# TELM0002ADC.net
KiCad netlist of a schematic drawn in Altium Designer
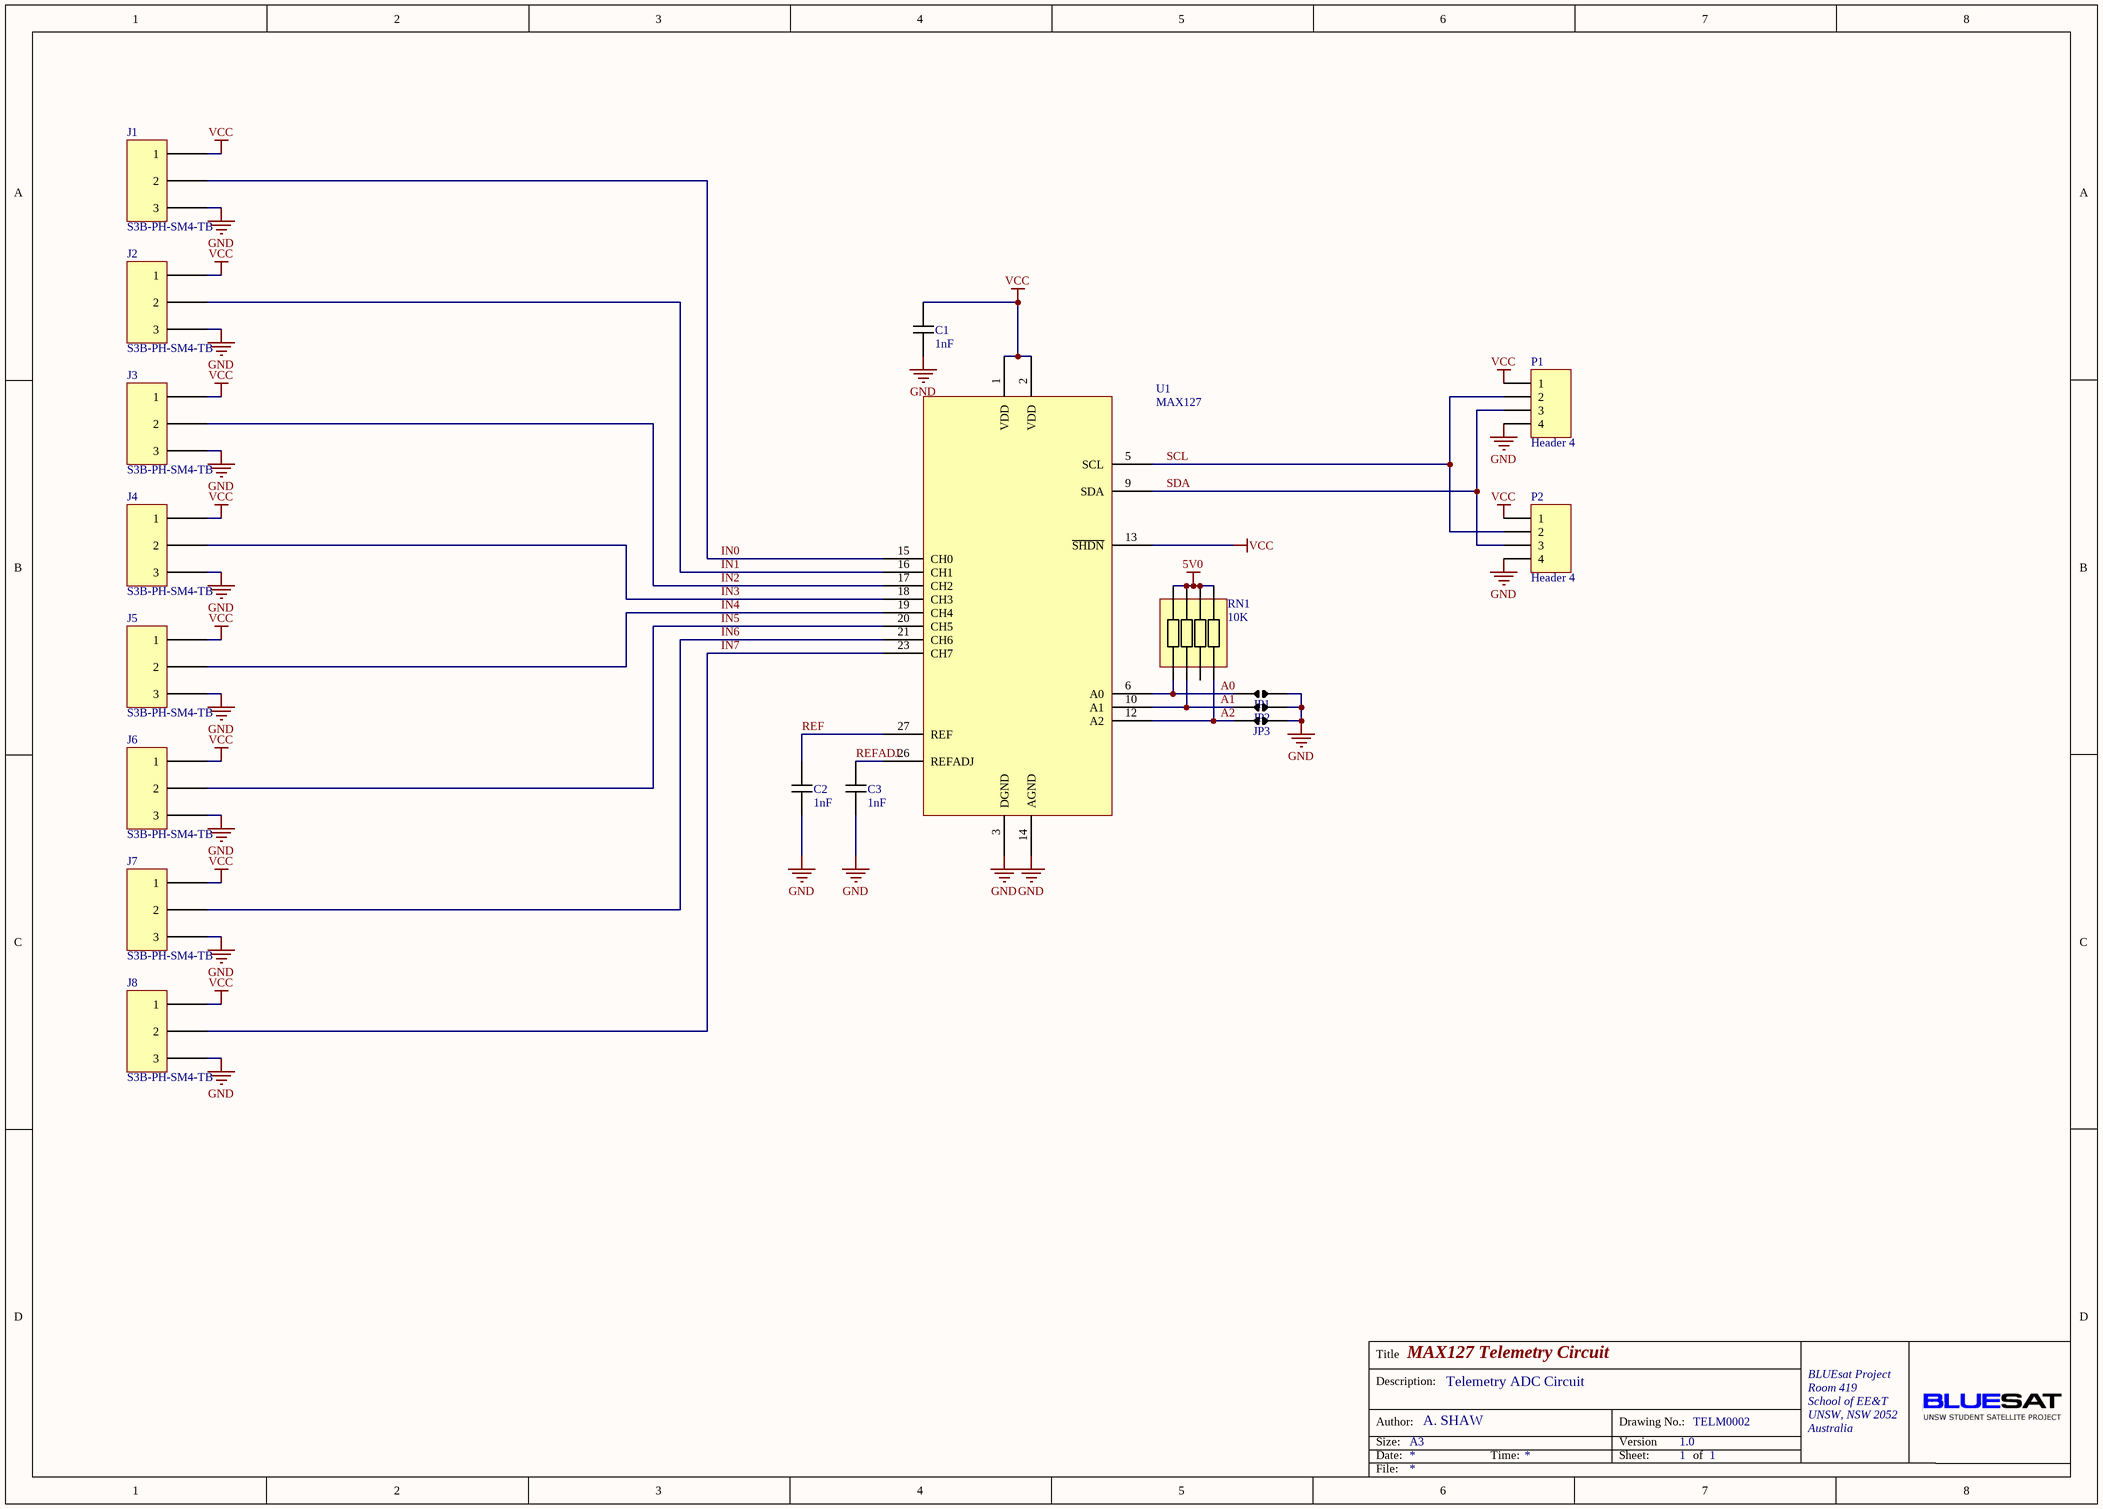
[diagram p0: TELM0002ADC.SchDoc]

(export (version "E")
  (design (tool "Eeschema 10.0.6"))
  (components
    (comp (ref "C1")
      (value "1nF")
      (footprint "1206 Cap")
      (description "1206 MLCC - X7R, 10%")
      (fields (field (name "Comment") "1206 Cap"))
      (libsource (lib "Schlib1") (part "1206 MLCC - X7R, 10%"))
    )
    (comp (ref "C2")
      (value "1nF")
      (footprint "1206 Cap")
      (description "1206 MLCC - X7R, 10%")
      (fields (field (name "Comment") "1206 Cap"))
      (libsource (lib "Schlib1") (part "1206 MLCC - X7R, 10%"))
    )
    (comp (ref "C3")
      (value "1nF")
      (footprint "1206 Cap")
      (description "1206 MLCC - X7R, 10%")
      (fields (field (name "Comment") "1206 Cap"))
      (libsource (lib "Schlib1") (part "1206 MLCC - X7R, 10%"))
    )
    (comp (ref "J1")
      (value "S3B-PH-SM4-TB")
      (footprint "S3B-PH-SM4-TB")
      (description "JST connector")
      (libsource (lib "Schlib1") (part "S3B-PH-SM4-TB"))
    )
    (comp (ref "J2")
      (value "S3B-PH-SM4-TB")
      (footprint "S3B-PH-SM4-TB")
      (description "JST connector")
      (libsource (lib "Schlib1") (part "S3B-PH-SM4-TB"))
    )
    (comp (ref "J3")
      (value "S3B-PH-SM4-TB")
      (footprint "S3B-PH-SM4-TB")
      (description "JST connector")
      (libsource (lib "Schlib1") (part "S3B-PH-SM4-TB"))
    )
    (comp (ref "J4")
      (value "S3B-PH-SM4-TB")
      (footprint "S3B-PH-SM4-TB")
      (description "JST connector")
      (libsource (lib "Schlib1") (part "S3B-PH-SM4-TB"))
    )
    (comp (ref "J5")
      (value "S3B-PH-SM4-TB")
      (footprint "S3B-PH-SM4-TB")
      (description "JST connector")
      (libsource (lib "Schlib1") (part "S3B-PH-SM4-TB"))
    )
    (comp (ref "J6")
      (value "S3B-PH-SM4-TB")
      (footprint "S3B-PH-SM4-TB")
      (description "JST connector")
      (libsource (lib "Schlib1") (part "S3B-PH-SM4-TB"))
    )
    (comp (ref "J7")
      (value "S3B-PH-SM4-TB")
      (footprint "S3B-PH-SM4-TB")
      (description "JST connector")
      (libsource (lib "Schlib1") (part "S3B-PH-SM4-TB"))
    )
    (comp (ref "J8")
      (value "S3B-PH-SM4-TB")
      (footprint "S3B-PH-SM4-TB")
      (description "JST connector")
      (libsource (lib "Schlib1") (part "S3B-PH-SM4-TB"))
    )
    (comp (ref "JP1")
      (value "Jumper")
      (footprint "Solder Jumper C")
      (description "Solder Bridge")
      (libsource (lib "Schlib1") (part "Solder Bridge"))
    )
    (comp (ref "JP2")
      (value "Jumper")
      (footprint "Solder Jumper C")
      (description "Solder Bridge")
      (libsource (lib "Schlib1") (part "Solder Bridge"))
    )
    (comp (ref "JP3")
      (value "Jumper")
      (footprint "Solder Jumper C")
      (description "Solder Bridge")
      (libsource (lib "Schlib1") (part "Solder Bridge"))
    )
    (comp (ref "P1")
      (value "Header 4")
      (footprint "HDR1X4")
      (description "Header, 4-Pin")
      (fields (field (name "PUBLISHER") "Altium Limited"))
      (libsource (lib "Miscellaneous Connectors") (part "Header 4"))
    )
    (comp (ref "P2")
      (value "Header 4")
      (footprint "HDR1X4")
      (description "Header, 4-Pin")
      (fields (field (name "PUBLISHER") "Altium Limited"))
      (libsource (lib "Miscellaneous Connectors") (part "Header 4"))
    )
    (comp (ref "RN1")
      (value "10K")
      (footprint "ACAS_0612_AC")
      (fields (field (name "Comment") "RN4"))
      (libsource (lib "Schlib1") (part "RN4"))
    )
    (comp (ref "U1")
      (value "MAX127")
      (footprint "SSOP28 - MAX127")
      (description "8 Channel, 12 bit, I2C DAS")
      (libsource (lib "Schlib1") (part "MAX127"))
    )
  )
  (nets
    (net (code "1") (name "/A0") (class "Default")
      (node (ref "JP1") (pin "1") (pinfunction "1_1") (pintype "passive"))
      (node (ref "RN1") (pin "1") (pinfunction "1_1") (pintype "passive"))
      (node (ref "U1") (pin "6") (pinfunction "A0_6") (pintype "passive"))
    )
    (net (code "2") (name "/A1") (class "Default")
      (node (ref "JP2") (pin "1") (pinfunction "1_1") (pintype "passive"))
      (node (ref "RN1") (pin "2") (pinfunction "2_2") (pintype "passive"))
      (node (ref "U1") (pin "10") (pinfunction "A1_10") (pintype "passive"))
    )
    (net (code "3") (name "/A2") (class "Default")
      (node (ref "JP3") (pin "1") (pinfunction "1_1") (pintype "passive"))
      (node (ref "RN1") (pin "4") (pinfunction "4_4") (pintype "passive"))
      (node (ref "U1") (pin "12") (pinfunction "A2_12") (pintype "passive"))
    )
    (net (code "4") (name "/IN0") (class "Default")
      (node (ref "J1") (pin "2") (pinfunction "2_2") (pintype "passive"))
      (node (ref "U1") (pin "15") (pinfunction "CH0_15") (pintype "passive"))
    )
    (net (code "5") (name "/IN1") (class "Default")
      (node (ref "J2") (pin "2") (pinfunction "2_2") (pintype "passive"))
      (node (ref "U1") (pin "16") (pinfunction "CH1_16") (pintype "passive"))
    )
    (net (code "6") (name "/IN2") (class "Default")
      (node (ref "J3") (pin "2") (pinfunction "2_2") (pintype "passive"))
      (node (ref "U1") (pin "17") (pinfunction "CH2_17") (pintype "passive"))
    )
    (net (code "7") (name "/IN3") (class "Default")
      (node (ref "J4") (pin "2") (pinfunction "2_2") (pintype "passive"))
      (node (ref "U1") (pin "18") (pinfunction "CH3_18") (pintype "passive"))
    )
    (net (code "8") (name "/IN4") (class "Default")
      (node (ref "J5") (pin "2") (pinfunction "2_2") (pintype "passive"))
      (node (ref "U1") (pin "19") (pinfunction "CH4_19") (pintype "passive"))
    )
    (net (code "9") (name "/IN5") (class "Default")
      (node (ref "J6") (pin "2") (pinfunction "2_2") (pintype "passive"))
      (node (ref "U1") (pin "20") (pinfunction "CH5_20") (pintype "passive"))
    )
    (net (code "10") (name "/IN6") (class "Default")
      (node (ref "J7") (pin "2") (pinfunction "2_2") (pintype "passive"))
      (node (ref "U1") (pin "21") (pinfunction "CH6_21") (pintype "passive"))
    )
    (net (code "11") (name "/IN7") (class "Default")
      (node (ref "J8") (pin "2") (pinfunction "2_2") (pintype "passive"))
      (node (ref "U1") (pin "23") (pinfunction "CH7_23") (pintype "passive"))
    )
    (net (code "12") (name "/REF") (class "Default")
      (node (ref "C2") (pin "2") (pinfunction "2_2") (pintype "passive"))
      (node (ref "U1") (pin "27") (pinfunction "REF_27") (pintype "passive"))
    )
    (net (code "13") (name "/REFADJ") (class "Default")
      (node (ref "C3") (pin "2") (pinfunction "2_2") (pintype "passive"))
      (node (ref "U1") (pin "26") (pinfunction "REFADJ_26") (pintype "passive"))
    )
    (net (code "14") (name "/SCL") (class "Default")
      (node (ref "P1") (pin "2") (pinfunction "2_2") (pintype "passive"))
      (node (ref "P2") (pin "2") (pinfunction "2_2") (pintype "passive"))
      (node (ref "U1") (pin "5") (pinfunction "SCL_5") (pintype "passive"))
    )
    (net (code "15") (name "/SDA") (class "Default")
      (node (ref "P1") (pin "3") (pinfunction "3_3") (pintype "passive"))
      (node (ref "P2") (pin "3") (pinfunction "3_3") (pintype "passive"))
      (node (ref "U1") (pin "9") (pinfunction "SDA_9") (pintype "passive"))
    )
    (net (code "16") (name "5V0") (class "Default")
      (node (ref "RN1") (pin "5") (pinfunction "5_5") (pintype "passive"))
      (node (ref "RN1") (pin "6") (pinfunction "6_6") (pintype "passive"))
      (node (ref "RN1") (pin "7") (pinfunction "7_7") (pintype "passive"))
      (node (ref "RN1") (pin "8") (pinfunction "8_8") (pintype "passive"))
    )
    (net (code "17") (name "GND") (class "Default")
      (node (ref "C1") (pin "1") (pinfunction "1_1") (pintype "passive"))
      (node (ref "C2") (pin "1") (pinfunction "1_1") (pintype "passive"))
      (node (ref "C3") (pin "1") (pinfunction "1_1") (pintype "passive"))
      (node (ref "J1") (pin "3") (pinfunction "3_3") (pintype "passive"))
      (node (ref "J2") (pin "3") (pinfunction "3_3") (pintype "passive"))
      (node (ref "J3") (pin "3") (pinfunction "3_3") (pintype "passive"))
      (node (ref "J4") (pin "3") (pinfunction "3_3") (pintype "passive"))
      (node (ref "J5") (pin "3") (pinfunction "3_3") (pintype "passive"))
      (node (ref "J6") (pin "3") (pinfunction "3_3") (pintype "passive"))
      (node (ref "J7") (pin "3") (pinfunction "3_3") (pintype "passive"))
      (node (ref "J8") (pin "3") (pinfunction "3_3") (pintype "passive"))
      (node (ref "JP1") (pin "2") (pinfunction "2_2") (pintype "passive"))
      (node (ref "JP2") (pin "2") (pinfunction "2_2") (pintype "passive"))
      (node (ref "JP3") (pin "2") (pinfunction "2_2") (pintype "passive"))
      (node (ref "P1") (pin "4") (pinfunction "4_4") (pintype "passive"))
      (node (ref "P2") (pin "4") (pinfunction "4_4") (pintype "passive"))
      (node (ref "U1") (pin "14") (pinfunction "AGND_14") (pintype "passive"))
      (node (ref "U1") (pin "3") (pinfunction "DGND_3") (pintype "passive"))
    )
    (net (code "18") (name "VCC") (class "Default")
      (node (ref "C1") (pin "2") (pinfunction "2_2") (pintype "passive"))
      (node (ref "J1") (pin "1") (pinfunction "1_1") (pintype "passive"))
      (node (ref "J2") (pin "1") (pinfunction "1_1") (pintype "passive"))
      (node (ref "J3") (pin "1") (pinfunction "1_1") (pintype "passive"))
      (node (ref "J4") (pin "1") (pinfunction "1_1") (pintype "passive"))
      (node (ref "J5") (pin "1") (pinfunction "1_1") (pintype "passive"))
      (node (ref "J6") (pin "1") (pinfunction "1_1") (pintype "passive"))
      (node (ref "J7") (pin "1") (pinfunction "1_1") (pintype "passive"))
      (node (ref "J8") (pin "1") (pinfunction "1_1") (pintype "passive"))
      (node (ref "P1") (pin "1") (pinfunction "1_1") (pintype "passive"))
      (node (ref "P2") (pin "1") (pinfunction "1_1") (pintype "passive"))
      (node (ref "U1") (pin "1") (pinfunction "VDD_1") (pintype "passive"))
      (node (ref "U1") (pin "13") (pinfunction "~{SHDN}_13") (pintype "passive"))
      (node (ref "U1") (pin "2") (pinfunction "VDD_2") (pintype "passive"))
    )
    (net (code "19") (name "unconnected-(RN1-Pad3)") (class "Default")
      (node (ref "RN1") (pin "3") (pinfunction "3_3") (pintype "passive"))
    )
  )
)
